# sch4.net
KiCad netlist of a schematic drawn in Altium Designer
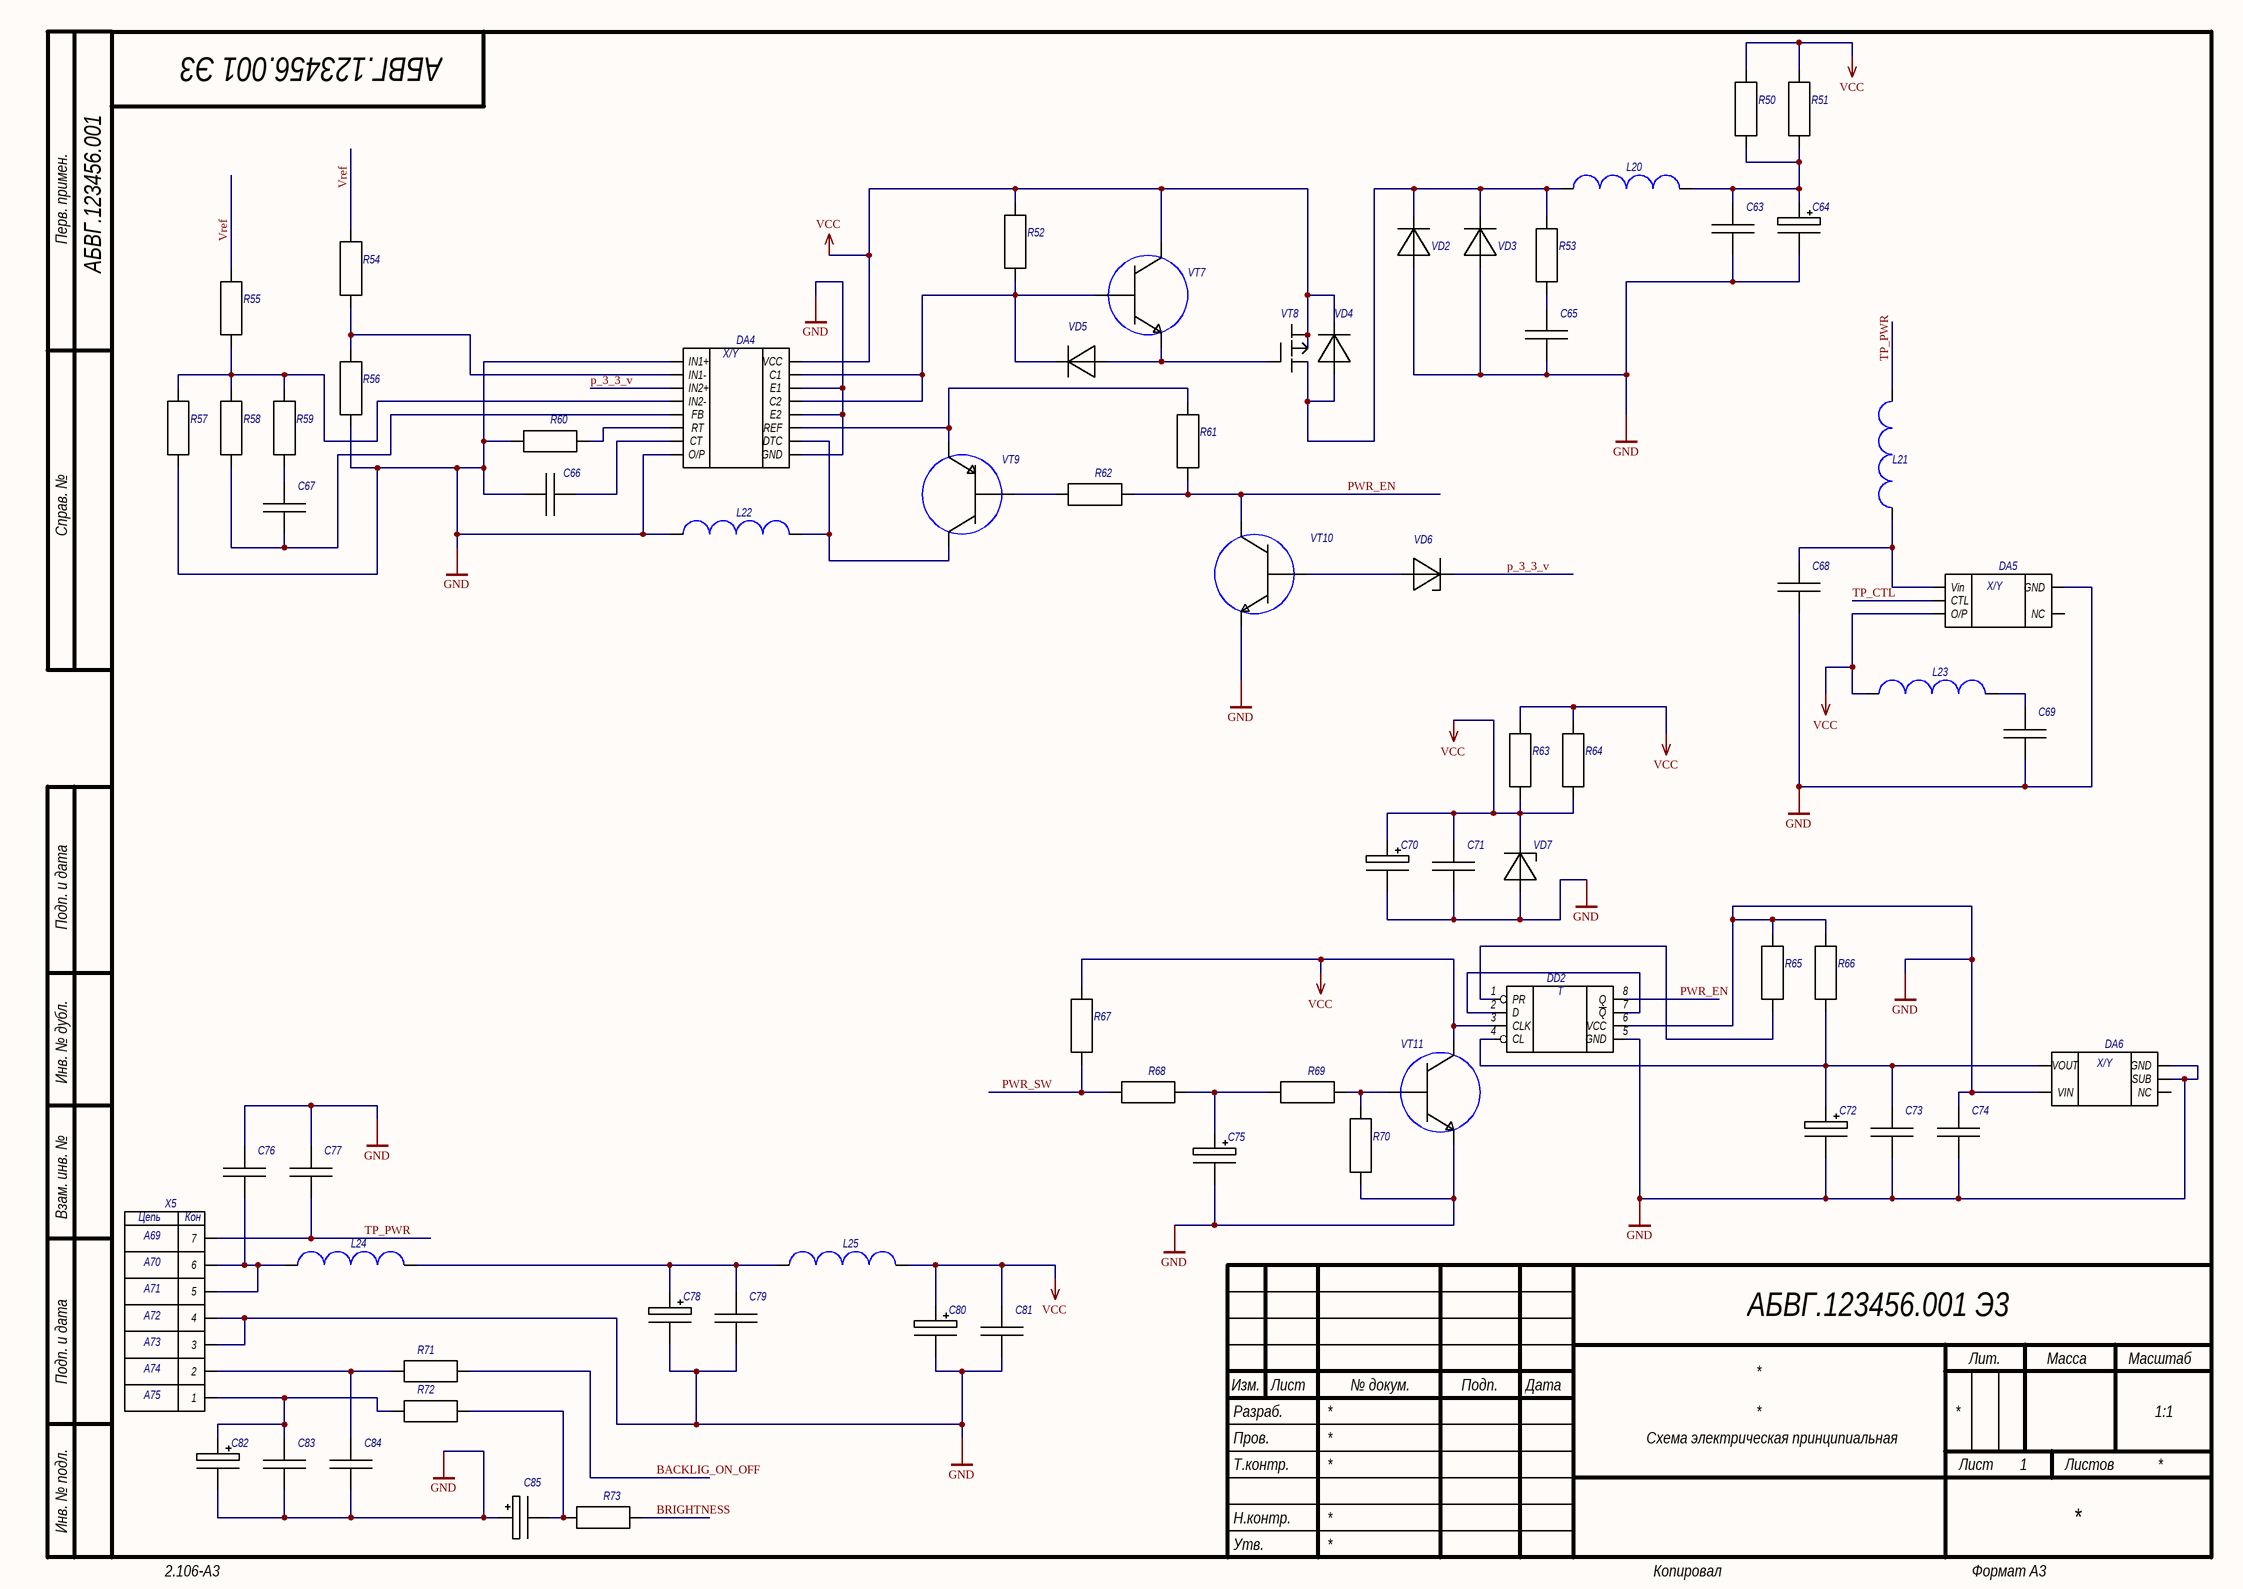
[diagram p0: sch4.SchDoc]

(export (version "E")
  (design (tool "Eeschema 10.0.6"))
  (components
    (comp (ref "C63")
      (value "*")
      (footprint "Capacitor 0805")
      (libsource (lib "k7shared") (part "Capacitor"))
    )
    (comp (ref "C64")
      (value "*")
      (footprint "Capacitor 0805")
      (libsource (lib "k7shared") (part "Capacitor Duga"))
    )
    (comp (ref "C65")
      (value "*")
      (footprint "Capacitor 0805")
      (libsource (lib "k7shared") (part "Capacitor"))
    )
    (comp (ref "C66")
      (value "*")
      (footprint "Capacitor 0805")
      (libsource (lib "k7shared") (part "Capacitor"))
    )
    (comp (ref "C67")
      (value "*")
      (footprint "Capacitor 0805")
      (libsource (lib "k7shared") (part "Capacitor"))
    )
    (comp (ref "C68")
      (value "*")
      (footprint "Capacitor 0805")
      (libsource (lib "k7shared") (part "Capacitor"))
    )
    (comp (ref "C69")
      (value "*")
      (footprint "Capacitor 0805")
      (libsource (lib "k7shared") (part "Capacitor"))
    )
    (comp (ref "C70")
      (value "*")
      (footprint "Capacitor 0805")
      (libsource (lib "k7shared") (part "Capacitor Duga"))
    )
    (comp (ref "C71")
      (value "*")
      (footprint "Capacitor 0805")
      (libsource (lib "k7shared") (part "Capacitor"))
    )
    (comp (ref "C72")
      (value "*")
      (footprint "Capacitor 0805")
      (libsource (lib "k7shared") (part "Capacitor Duga"))
    )
    (comp (ref "C73")
      (value "*")
      (footprint "Capacitor 0805")
      (libsource (lib "k7shared") (part "Capacitor"))
    )
    (comp (ref "C74")
      (value "*")
      (footprint "Capacitor 0805")
      (libsource (lib "k7shared") (part "Capacitor"))
    )
    (comp (ref "C75")
      (value "*")
      (footprint "Capacitor 0805")
      (libsource (lib "k7shared") (part "Capacitor Duga"))
    )
    (comp (ref "C76")
      (value "*")
      (footprint "Capacitor 0805")
      (libsource (lib "k7shared") (part "Capacitor"))
    )
    (comp (ref "C77")
      (value "*")
      (footprint "Capacitor 0805")
      (libsource (lib "k7shared") (part "Capacitor"))
    )
    (comp (ref "C78")
      (value "*")
      (footprint "Capacitor 0805")
      (libsource (lib "k7shared") (part "Capacitor Duga"))
    )
    (comp (ref "C79")
      (value "*")
      (footprint "Capacitor 0805")
      (libsource (lib "k7shared") (part "Capacitor"))
    )
    (comp (ref "C80")
      (value "*")
      (footprint "Capacitor 0805")
      (libsource (lib "k7shared") (part "Capacitor Duga"))
    )
    (comp (ref "C81")
      (value "*")
      (footprint "Capacitor 0805")
      (libsource (lib "k7shared") (part "Capacitor"))
    )
    (comp (ref "C82")
      (value "*")
      (footprint "Capacitor 0805")
      (libsource (lib "k7shared") (part "Capacitor Duga"))
    )
    (comp (ref "C83")
      (value "*")
      (footprint "Capacitor 0805")
      (libsource (lib "k7shared") (part "Capacitor"))
    )
    (comp (ref "C84")
      (value "*")
      (footprint "Capacitor 0805")
      (libsource (lib "k7shared") (part "Capacitor"))
    )
    (comp (ref "C85")
      (value "*")
      (footprint "Capacitor 0805")
      (libsource (lib "k7shared") (part "Capacitor Duga"))
    )
    (comp (ref "DA4") (value "*") (footprint "AP494A_1") (libsource (lib "k7sch4") (part "AP494A")))
    (comp (ref "DA5") (value "*") (footprint "PQ05") (libsource (lib "k7sch4") (part "PQ05")))
    (comp (ref "DA6") (value "IC103") (footprint "IC103_2") (libsource (lib "k7sch3") (part "IC103")))
    (comp (ref "DD2") (value "*") (footprint "D FF") (libsource (lib "k7sch4") (part "74F74")))
    (comp (ref "L20") (value "*") (footprint "Inductor 2520") (libsource (lib "k7shared") (part "Inductor")))
    (comp (ref "L21") (value "*") (footprint "Inductor 2520") (libsource (lib "") (part "Inductor_1")))
    (comp (ref "L22") (value "*") (footprint "Inductor 2520") (libsource (lib "k7shared") (part "Inductor")))
    (comp (ref "L23") (value "*") (footprint "Inductor 2520") (libsource (lib "k7shared") (part "Inductor")))
    (comp (ref "L24") (value "*") (footprint "Inductor 2520") (libsource (lib "k7shared") (part "Inductor")))
    (comp (ref "L25") (value "*") (footprint "Inductor 2520") (libsource (lib "k7shared") (part "Inductor")))
    (comp (ref "R50") (value "*") (footprint "Resistor 1206") (libsource (lib "k7shared") (part "Resistor")))
    (comp (ref "R51") (value "*") (footprint "Resistor 1206") (libsource (lib "k7shared") (part "Resistor")))
    (comp (ref "R52") (value "*") (footprint "Resistor 1206") (libsource (lib "k7shared") (part "Resistor")))
    (comp (ref "R53") (value "*") (footprint "Resistor 1206") (libsource (lib "k7shared") (part "Resistor")))
    (comp (ref "R54") (value "*") (footprint "Resistor 1206") (libsource (lib "k7shared") (part "Resistor")))
    (comp (ref "R55") (value "*") (footprint "Resistor 1206") (libsource (lib "k7shared") (part "Resistor")))
    (comp (ref "R56") (value "*") (footprint "Resistor 1206") (libsource (lib "k7shared") (part "Resistor")))
    (comp (ref "R57") (value "*") (footprint "Resistor 1206") (libsource (lib "k7shared") (part "Resistor")))
    (comp (ref "R58") (value "*") (footprint "Resistor 1206") (libsource (lib "k7shared") (part "Resistor")))
    (comp (ref "R59") (value "*") (footprint "Resistor 1206") (libsource (lib "k7shared") (part "Resistor")))
    (comp (ref "R60") (value "*") (footprint "Resistor 1206") (libsource (lib "k7shared") (part "Resistor")))
    (comp (ref "R61") (value "*") (footprint "Resistor 1206") (libsource (lib "k7shared") (part "Resistor")))
    (comp (ref "R62") (value "*") (footprint "Resistor 1206") (libsource (lib "k7shared") (part "Resistor")))
    (comp (ref "R63") (value "*") (footprint "Resistor 1206") (libsource (lib "k7shared") (part "Resistor")))
    (comp (ref "R64") (value "*") (footprint "Resistor 1206") (libsource (lib "k7shared") (part "Resistor")))
    (comp (ref "R65") (value "*") (footprint "Resistor 1206") (libsource (lib "k7shared") (part "Resistor")))
    (comp (ref "R66") (value "*") (footprint "Resistor 1206") (libsource (lib "k7shared") (part "Resistor")))
    (comp (ref "R67") (value "*") (footprint "Resistor 1206") (libsource (lib "k7shared") (part "Resistor")))
    (comp (ref "R68") (value "*") (footprint "Resistor 1206") (libsource (lib "k7shared") (part "Resistor")))
    (comp (ref "R69") (value "*") (footprint "Resistor 1206") (libsource (lib "k7shared") (part "Resistor")))
    (comp (ref "R70") (value "*") (footprint "Resistor 1206") (libsource (lib "k7shared") (part "Resistor")))
    (comp (ref "R71") (value "*") (footprint "Resistor 1206") (libsource (lib "k7shared") (part "Resistor")))
    (comp (ref "R72") (value "*") (footprint "Resistor 1206") (libsource (lib "k7shared") (part "Resistor")))
    (comp (ref "R73") (value "*") (footprint "Resistor 1206") (libsource (lib "k7shared") (part "Resistor")))
    (comp (ref "VD2") (value "*") (footprint "Diode") (libsource (lib "k7shared") (part "Diode 1")))
    (comp (ref "VD3") (value "*") (footprint "Diode") (libsource (lib "k7shared") (part "Diode 1")))
    (comp (ref "VD4") (value "Diode 1") (footprint "Diode") (libsource (lib "k7shared") (part "Diode 1")))
    (comp (ref "VD5") (value "*") (footprint "Diode") (libsource (lib "k7shared") (part "Diode 1")))
    (comp (ref "VD6") (value "*") (footprint "Diode") (libsource (lib "k7shared") (part "Diode 2")))
    (comp (ref "VD7") (value "*") (footprint "Diode") (libsource (lib "k7shared") (part "Diode 2")))
    (comp (ref "VT7")
      (value "*")
      (footprint "Transistor 1")
      (libsource (lib "k7shared") (part "Transistor 1"))
    )
    (comp (ref "VT8")
      (value "MOP TRANSISTOR")
      (footprint "TR")
      (libsource (lib "k7shared") (part "MOP TRANSISTOR"))
    )
    (comp (ref "VT9")
      (value "*")
      (footprint "Transistor 1")
      (libsource (lib "k7shared") (part "Transistor 1_1"))
    )
    (comp (ref "VT10")
      (value "*")
      (footprint "Transistor 1")
      (libsource (lib "k7shared") (part "Transistor 2_1"))
    )
    (comp (ref "VT11")
      (value "*")
      (footprint "Transistor 1")
      (libsource (lib "k7shared") (part "Transistor 1"))
    )
    (comp (ref "X5") (value "*") (footprint "J601") (libsource (lib "k7sch4") (part "J601")))
  )
  (nets
    (net (code "1") (name "/BACKLIG_ON_OFF") (class "Default")
      (node (ref "R71") (pin "2") (pinfunction "2_2") (pintype "passive"))
    )
    (net (code "2") (name "/BRIGHTNESS") (class "Default")
      (node (ref "R73") (pin "2") (pinfunction "2_2") (pintype "passive"))
    )
    (net (code "3") (name "/PWR_EN") (class "Default")
      (node (ref "DD2") (pin "8") (pinfunction "Q_8") (pintype "passive"))
      (node (ref "R61") (pin "1") (pinfunction "1_1") (pintype "passive"))
      (node (ref "R62") (pin "2") (pinfunction "2_2") (pintype "passive"))
      (node (ref "VT10") (pin "1") (pinfunction "KOLLECTOR_1") (pintype "passive"))
    )
    (net (code "4") (name "/PWR_SW") (class "Default")
      (node (ref "R67") (pin "1") (pinfunction "1_1") (pintype "passive"))
      (node (ref "R68") (pin "1") (pinfunction "1_1") (pintype "passive"))
    )
    (net (code "5") (name "/TP_CTL") (class "Default")
      (node (ref "DA5") (pin "2") (pinfunction "CTL_2") (pintype "passive"))
    )
    (net (code "6") (name "/TP_PWR") (class "Default")
      (node (ref "C77") (pin "1") (pinfunction "1_1") (pintype "passive"))
      (node (ref "L21") (pin "2") (pinfunction "2_2") (pintype "passive"))
      (node (ref "X5") (pin "7") (pinfunction "7_7") (pintype "passive"))
    )
    (net (code "7") (name "/Vref") (class "Default")
      (node (ref "R54") (pin "2") (pinfunction "2_2") (pintype "passive"))
      (node (ref "R55") (pin "2") (pinfunction "2_2") (pintype "passive"))
    )
    (net (code "8") (name "/p_3_3_v") (class "Default")
      (node (ref "DA4") (pin "3") (pinfunction "IN2+_3") (pintype "passive"))
      (node (ref "VD6") (pin "2") (pinfunction "2_2") (pintype "passive"))
    )
    (net (code "9") (name "GND") (class "Default")
      (node (ref "C63") (pin "1") (pinfunction "1_1") (pintype "passive"))
      (node (ref "C64") (pin "1") (pinfunction "1_1") (pintype "passive"))
      (node (ref "C65") (pin "1") (pinfunction "1_1") (pintype "passive"))
      (node (ref "C66") (pin "2") (pinfunction "2_2") (pintype "passive"))
      (node (ref "C68") (pin "1") (pinfunction "1_1") (pintype "passive"))
      (node (ref "C69") (pin "1") (pinfunction "1_1") (pintype "passive"))
      (node (ref "C70") (pin "1") (pinfunction "1_1") (pintype "passive"))
      (node (ref "C71") (pin "1") (pinfunction "1_1") (pintype "passive"))
      (node (ref "C72") (pin "1") (pinfunction "1_1") (pintype "passive"))
      (node (ref "C73") (pin "1") (pinfunction "1_1") (pintype "passive"))
      (node (ref "C74") (pin "1") (pinfunction "1_1") (pintype "passive"))
      (node (ref "C74") (pin "2") (pinfunction "2_2") (pintype "passive"))
      (node (ref "C75") (pin "1") (pinfunction "1_1") (pintype "passive"))
      (node (ref "C76") (pin "2") (pinfunction "2_2") (pintype "passive"))
      (node (ref "C77") (pin "2") (pinfunction "2_2") (pintype "passive"))
      (node (ref "C78") (pin "1") (pinfunction "1_1") (pintype "passive"))
      (node (ref "C79") (pin "1") (pinfunction "1_1") (pintype "passive"))
      (node (ref "C80") (pin "1") (pinfunction "1_1") (pintype "passive"))
      (node (ref "C81") (pin "1") (pinfunction "1_1") (pintype "passive"))
      (node (ref "C82") (pin "1") (pinfunction "1_1") (pintype "passive"))
      (node (ref "C83") (pin "1") (pinfunction "1_1") (pintype "passive"))
      (node (ref "C84") (pin "1") (pinfunction "1_1") (pintype "passive"))
      (node (ref "C85") (pin "2") (pinfunction "2_2") (pintype "passive"))
      (node (ref "DA4") (pin "1") (pinfunction "IN1+_1") (pintype "passive"))
      (node (ref "DA4") (pin "12") (pinfunction "E2_12") (pintype "passive"))
      (node (ref "DA4") (pin "14") (pinfunction "E1_14") (pintype "passive"))
      (node (ref "DA4") (pin "8") (pinfunction "O/P_8") (pintype "passive"))
      (node (ref "DA4") (pin "9") (pinfunction "GND_9") (pintype "passive"))
      (node (ref "DA5") (pin "5") (pinfunction "GND_5") (pintype "passive"))
      (node (ref "DA6") (pin "1") (pinfunction "GND_1") (pintype "passive"))
      (node (ref "DA6") (pin "2") (pinfunction "SUB_2") (pintype "passive"))
      (node (ref "DA6") (pin "5") (pinfunction "VIN_5") (pintype "passive"))
      (node (ref "DD2") (pin "5") (pinfunction "GND_5") (pintype "passive"))
      (node (ref "DD2") (pin "6") (pinfunction "VCC_6") (pintype "passive"))
      (node (ref "L22") (pin "1") (pinfunction "1_1") (pintype "passive"))
      (node (ref "R56") (pin "1") (pinfunction "1_1") (pintype "passive"))
      (node (ref "R57") (pin "1") (pinfunction "1_1") (pintype "passive"))
      (node (ref "R60") (pin "1") (pinfunction "1_1") (pintype "passive"))
      (node (ref "R65") (pin "2") (pinfunction "2_2") (pintype "passive"))
      (node (ref "R66") (pin "2") (pinfunction "2_2") (pintype "passive"))
      (node (ref "R70") (pin "1") (pinfunction "1_1") (pintype "passive"))
      (node (ref "VD2") (pin "1") (pinfunction "1_1") (pintype "passive"))
      (node (ref "VD3") (pin "1") (pinfunction "1_1") (pintype "passive"))
      (node (ref "VD7") (pin "1") (pinfunction "1_1") (pintype "passive"))
      (node (ref "VT10") (pin "2") (pinfunction "EMITTER_2") (pintype "passive"))
      (node (ref "VT11") (pin "1") (pinfunction "KOLLECTOR_1") (pintype "passive"))
      (node (ref "X5") (pin "3") (pinfunction "3_3") (pintype "passive"))
      (node (ref "X5") (pin "4") (pinfunction "4_4") (pintype "passive"))
    )
    (net (code "10") (name "Net-(C63-Pad2)") (class "Default")
      (node (ref "C63") (pin "2") (pinfunction "2_2") (pintype "passive"))
      (node (ref "C64") (pin "2") (pinfunction "2_2") (pintype "passive"))
      (node (ref "L20") (pin "2") (pinfunction "2_2") (pintype "passive"))
      (node (ref "R50") (pin "1") (pinfunction "1_1") (pintype "passive"))
      (node (ref "R51") (pin "1") (pinfunction "1_1") (pintype "passive"))
    )
    (net (code "11") (name "Net-(C65-Pad2)") (class "Default")
      (node (ref "C65") (pin "2") (pinfunction "2_2") (pintype "passive"))
      (node (ref "R53") (pin "1") (pinfunction "1_1") (pintype "passive"))
    )
    (net (code "12") (name "Net-(C67-Pad2)") (class "Default")
      (node (ref "C67") (pin "2") (pinfunction "2_2") (pintype "passive"))
      (node (ref "R59") (pin "1") (pinfunction "1_1") (pintype "passive"))
    )
    (net (code "13") (name "Net-(C69-Pad2)") (class "Default")
      (node (ref "C69") (pin "2") (pinfunction "2_2") (pintype "passive"))
      (node (ref "L23") (pin "2") (pinfunction "2_2") (pintype "passive"))
    )
    (net (code "14") (name "Net-(C75-Pad2)") (class "Default")
      (node (ref "C75") (pin "2") (pinfunction "2_2") (pintype "passive"))
      (node (ref "R68") (pin "2") (pinfunction "2_2") (pintype "passive"))
      (node (ref "R69") (pin "1") (pinfunction "1_1") (pintype "passive"))
    )
    (net (code "15") (name "Net-(C76-Pad1)") (class "Default")
      (node (ref "C76") (pin "1") (pinfunction "1_1") (pintype "passive"))
      (node (ref "L24") (pin "1") (pinfunction "1_1") (pintype "passive"))
      (node (ref "X5") (pin "5") (pinfunction "5_5") (pintype "passive"))
      (node (ref "X5") (pin "6") (pinfunction "6_6") (pintype "passive"))
    )
    (net (code "16") (name "Net-(C78-Pad2)") (class "Default")
      (node (ref "C78") (pin "2") (pinfunction "2_2") (pintype "passive"))
      (node (ref "C79") (pin "2") (pinfunction "2_2") (pintype "passive"))
      (node (ref "L24") (pin "2") (pinfunction "2_2") (pintype "passive"))
      (node (ref "L25") (pin "1") (pinfunction "1_1") (pintype "passive"))
    )
    (net (code "17") (name "Net-(C82-Pad2)") (class "Default")
      (node (ref "C82") (pin "2") (pinfunction "2_2") (pintype "passive"))
      (node (ref "C83") (pin "2") (pinfunction "2_2") (pintype "passive"))
      (node (ref "R72") (pin "1") (pinfunction "1_1") (pintype "passive"))
      (node (ref "X5") (pin "1") (pinfunction "1_1") (pintype "passive"))
    )
    (net (code "18") (name "Net-(C84-Pad2)") (class "Default")
      (node (ref "C84") (pin "2") (pinfunction "2_2") (pintype "passive"))
      (node (ref "R71") (pin "1") (pinfunction "1_1") (pintype "passive"))
      (node (ref "X5") (pin "2") (pinfunction "2_2") (pintype "passive"))
    )
    (net (code "19") (name "Net-(C85-Pad1)") (class "Default")
      (node (ref "C85") (pin "1") (pinfunction "1_1") (pintype "passive"))
      (node (ref "R72") (pin "2") (pinfunction "2_2") (pintype "passive"))
      (node (ref "R73") (pin "1") (pinfunction "1_1") (pintype "passive"))
    )
    (net (code "20") (name "Net-(DA4-C1)") (class "Default")
      (node (ref "DA4") (pin "13") (pinfunction "C2_13") (pintype "passive"))
      (node (ref "DA4") (pin "15") (pinfunction "C1_15") (pintype "passive"))
      (node (ref "R52") (pin "1") (pinfunction "1_1") (pintype "passive"))
      (node (ref "VD5") (pin "2") (pinfunction "2_2") (pintype "passive"))
      (node (ref "VT7") (pin "3") (pinfunction "BAZA_3") (pintype "passive"))
    )
    (net (code "21") (name "Net-(DA4-CT)") (class "Default")
      (node (ref "C66") (pin "1") (pinfunction "1_1") (pintype "passive"))
      (node (ref "DA4") (pin "7") (pinfunction "CT_7") (pintype "passive"))
    )
    (net (code "22") (name "Net-(DA4-DTC)") (class "Default")
      (node (ref "DA4") (pin "10") (pinfunction "DTC_10") (pintype "passive"))
      (node (ref "L22") (pin "2") (pinfunction "2_2") (pintype "passive"))
      (node (ref "VT9") (pin "2") (pinfunction "EMITTER_2") (pintype "passive"))
    )
    (net (code "23") (name "Net-(DA4-FB)") (class "Default")
      (node (ref "C67") (pin "1") (pinfunction "1_1") (pintype "passive"))
      (node (ref "DA4") (pin "5") (pinfunction "FB_5") (pintype "passive"))
      (node (ref "R58") (pin "1") (pinfunction "1_1") (pintype "passive"))
    )
    (net (code "24") (name "Net-(DA4-IN1-)") (class "Default")
      (node (ref "DA4") (pin "2") (pinfunction "IN1-_2") (pintype "passive"))
      (node (ref "R54") (pin "1") (pinfunction "1_1") (pintype "passive"))
      (node (ref "R56") (pin "2") (pinfunction "2_2") (pintype "passive"))
    )
    (net (code "25") (name "Net-(DA4-IN2-)") (class "Default")
      (node (ref "DA4") (pin "4") (pinfunction "IN2-_4") (pintype "passive"))
      (node (ref "R55") (pin "1") (pinfunction "1_1") (pintype "passive"))
      (node (ref "R57") (pin "2") (pinfunction "2_2") (pintype "passive"))
      (node (ref "R58") (pin "2") (pinfunction "2_2") (pintype "passive"))
      (node (ref "R59") (pin "2") (pinfunction "2_2") (pintype "passive"))
    )
    (net (code "26") (name "Net-(DA4-REF)") (class "Default")
      (node (ref "DA4") (pin "11") (pinfunction "REF_11") (pintype "passive"))
      (node (ref "R61") (pin "2") (pinfunction "2_2") (pintype "passive"))
      (node (ref "VT9") (pin "1") (pinfunction "KOLLECTOR_1") (pintype "passive"))
    )
    (net (code "27") (name "Net-(DA4-RT)") (class "Default")
      (node (ref "DA4") (pin "6") (pinfunction "RT_6") (pintype "passive"))
      (node (ref "R60") (pin "2") (pinfunction "2_2") (pintype "passive"))
    )
    (net (code "28") (name "Net-(DA5-Vin)") (class "Default")
      (node (ref "C68") (pin "2") (pinfunction "2_2") (pintype "passive"))
      (node (ref "DA5") (pin "1") (pinfunction "Vin_1") (pintype "passive"))
      (node (ref "L21") (pin "1") (pinfunction "1_1") (pintype "passive"))
    )
    (net (code "29") (name "Net-(DA6-VOUT)") (class "Default")
      (node (ref "C72") (pin "2") (pinfunction "2_2") (pintype "passive"))
      (node (ref "C73") (pin "2") (pinfunction "2_2") (pintype "passive"))
      (node (ref "DA6") (pin "4") (pinfunction "VOUT_4") (pintype "passive"))
      (node (ref "DD2") (pin "4") (pinfunction "CL_4") (pintype "passive"))
      (node (ref "R66") (pin "1") (pinfunction "1_1") (pintype "passive"))
    )
    (net (code "30") (name "Net-(DD2-D)") (class "Default")
      (node (ref "DD2") (pin "2") (pinfunction "D_2") (pintype "passive"))
      (node (ref "DD2") (pin "7") (pinfunction "~{Q}_7") (pintype "passive"))
    )
    (net (code "31") (name "Net-(DD2-PR)") (class "Default")
      (node (ref "DD2") (pin "1") (pinfunction "PR_1") (pintype "passive"))
      (node (ref "R65") (pin "1") (pinfunction "1_1") (pintype "passive"))
    )
    (net (code "32") (name "Net-(L20-Pad1)") (class "Default")
      (node (ref "L20") (pin "1") (pinfunction "1_1") (pintype "passive"))
      (node (ref "R53") (pin "2") (pinfunction "2_2") (pintype "passive"))
      (node (ref "VD2") (pin "2") (pinfunction "2_2") (pintype "passive"))
      (node (ref "VD3") (pin "2") (pinfunction "2_2") (pintype "passive"))
      (node (ref "VD4") (pin "1") (pinfunction "1_1") (pintype "passive"))
      (node (ref "VT8") (pin "2") (pinfunction "2_2") (pintype "passive"))
    )
    (net (code "33") (name "Net-(VT7-KOLLECTOR)") (class "Default")
      (node (ref "VD5") (pin "1") (pinfunction "1_1") (pintype "passive"))
      (node (ref "VT7") (pin "1") (pinfunction "KOLLECTOR_1") (pintype "passive"))
      (node (ref "VT8") (pin "1") (pinfunction "1_1") (pintype "passive"))
    )
    (net (code "34") (name "Net-(VT9-BAZA)") (class "Default")
      (node (ref "R62") (pin "1") (pinfunction "1_1") (pintype "passive"))
      (node (ref "VT9") (pin "3") (pinfunction "BAZA_3") (pintype "passive"))
    )
    (net (code "35") (name "Net-(VT10-BAZA)") (class "Default")
      (node (ref "VD6") (pin "1") (pinfunction "1_1") (pintype "passive"))
      (node (ref "VT10") (pin "3") (pinfunction "BAZA_3") (pintype "passive"))
    )
    (net (code "36") (name "Net-(VT11-BAZA)") (class "Default")
      (node (ref "R69") (pin "2") (pinfunction "2_2") (pintype "passive"))
      (node (ref "R70") (pin "2") (pinfunction "2_2") (pintype "passive"))
      (node (ref "VT11") (pin "3") (pinfunction "BAZA_3") (pintype "passive"))
    )
    (net (code "37") (name "VCC") (class "Default")
      (node (ref "C70") (pin "2") (pinfunction "2_2") (pintype "passive"))
      (node (ref "C71") (pin "2") (pinfunction "2_2") (pintype "passive"))
      (node (ref "C80") (pin "2") (pinfunction "2_2") (pintype "passive"))
      (node (ref "C81") (pin "2") (pinfunction "2_2") (pintype "passive"))
      (node (ref "DA4") (pin "16") (pinfunction "VCC_16") (pintype "passive"))
      (node (ref "DA5") (pin "3") (pinfunction "O/P_3") (pintype "passive"))
      (node (ref "DD2") (pin "3") (pinfunction "CLK_3") (pintype "passive"))
      (node (ref "L23") (pin "1") (pinfunction "1_1") (pintype "passive"))
      (node (ref "L25") (pin "2") (pinfunction "2_2") (pintype "passive"))
      (node (ref "R50") (pin "2") (pinfunction "2_2") (pintype "passive"))
      (node (ref "R51") (pin "2") (pinfunction "2_2") (pintype "passive"))
      (node (ref "R52") (pin "2") (pinfunction "2_2") (pintype "passive"))
      (node (ref "R63") (pin "1") (pinfunction "1_1") (pintype "passive"))
      (node (ref "R63") (pin "2") (pinfunction "2_2") (pintype "passive"))
      (node (ref "R64") (pin "1") (pinfunction "1_1") (pintype "passive"))
      (node (ref "R64") (pin "2") (pinfunction "2_2") (pintype "passive"))
      (node (ref "R67") (pin "2") (pinfunction "2_2") (pintype "passive"))
      (node (ref "VD4") (pin "2") (pinfunction "2_2") (pintype "passive"))
      (node (ref "VD7") (pin "2") (pinfunction "2_2") (pintype "passive"))
      (node (ref "VT11") (pin "2") (pinfunction "EMITTER_2") (pintype "passive"))
      (node (ref "VT7") (pin "2") (pinfunction "EMITTER_2") (pintype "passive"))
      (node (ref "VT8") (pin "3") (pinfunction "3_3") (pintype "passive"))
      (node (ref "VT8") (pin "4") (pinfunction "4_4") (pintype "passive"))
    )
    (net (code "38") (name "unconnected-(DA5-NC-Pad4)") (class "Default")
      (node (ref "DA5") (pin "4") (pinfunction "NC_4") (pintype "passive"))
    )
    (net (code "39") (name "unconnected-(DA6-NC-Pad3)") (class "Default")
      (node (ref "DA6") (pin "3") (pinfunction "NC_3") (pintype "passive"))
    )
  )
)
